# K60P144.net
KiCad netlist of a schematic drawn in Altium Designer
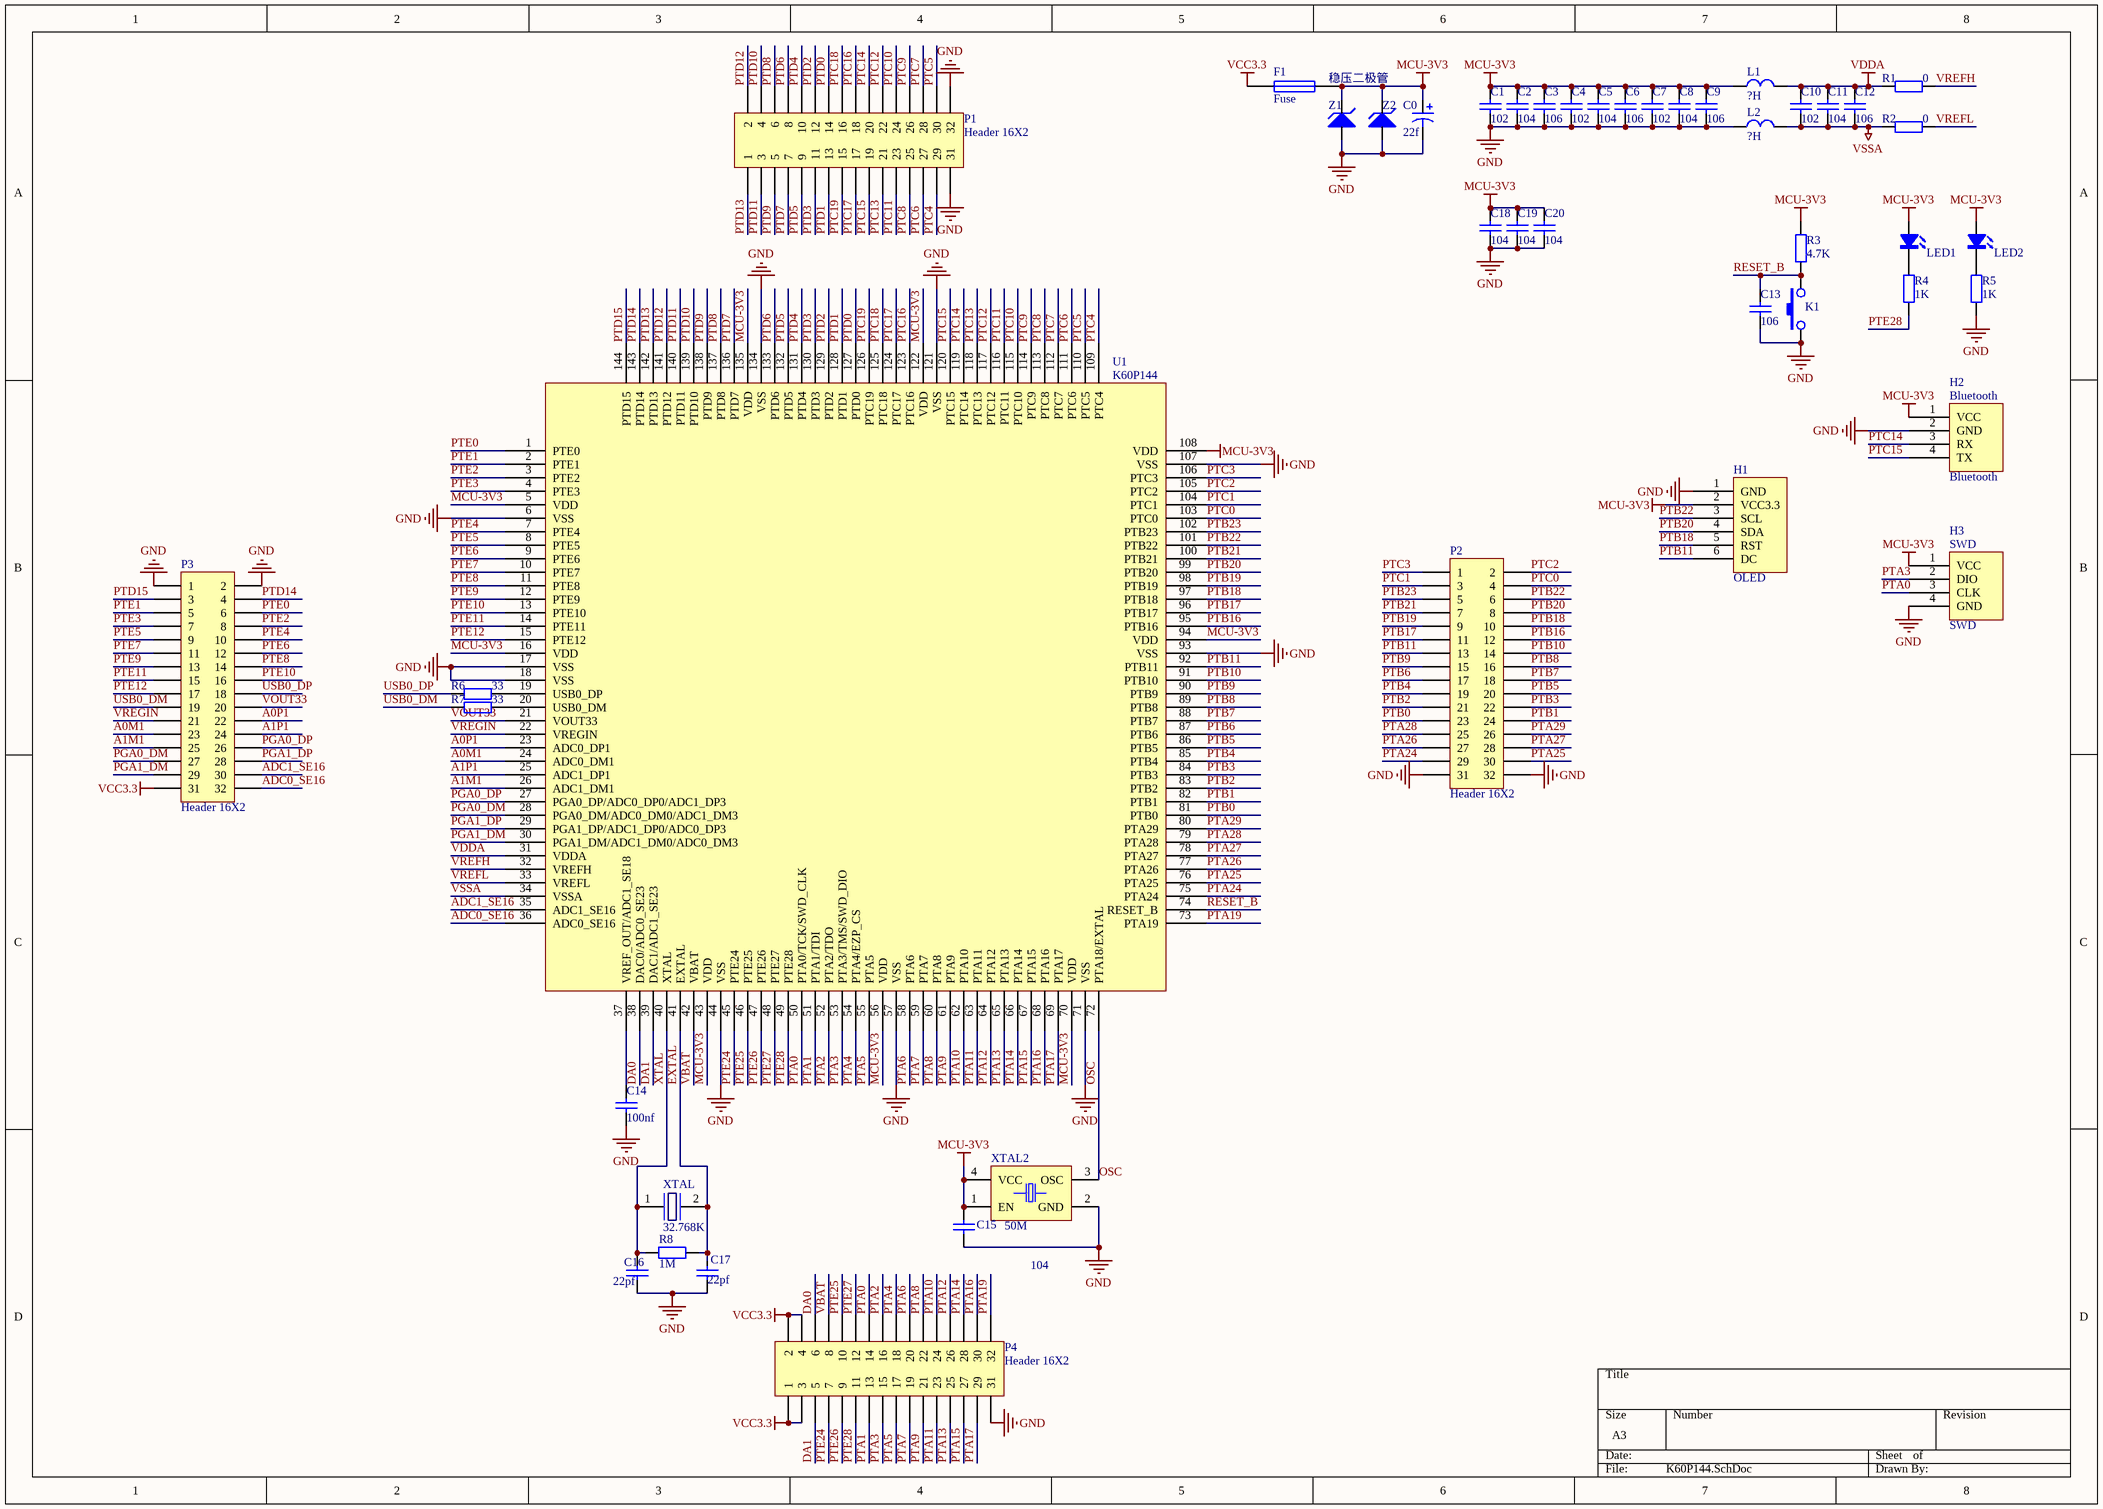
[diagram p0: K60P144.SchDoc]

(export (version "E")
  (design (tool "Eeschema 10.0.6"))
  (components
    (comp (ref "C0") (value "22f") (footprint "3528-B-TA") (libsource (lib "Bigbear") (part "CAP-TAN")))
    (comp (ref "C1") (value "102") (footprint "0805-0C") (libsource (lib "Bigbear") (part "CAP")))
    (comp (ref "C2") (value "104") (footprint "0805-0C") (libsource (lib "Bigbear") (part "CAP")))
    (comp (ref "C3") (value "106") (footprint "0805-0C") (libsource (lib "Bigbear") (part "CAP")))
    (comp (ref "C4") (value "102") (footprint "0805-0C") (libsource (lib "Bigbear") (part "CAP")))
    (comp (ref "C5") (value "104") (footprint "0805-0C") (libsource (lib "Bigbear") (part "CAP")))
    (comp (ref "C6") (value "106") (footprint "0805-0C") (libsource (lib "Bigbear") (part "CAP")))
    (comp (ref "C7") (value "102") (footprint "0805-0C") (libsource (lib "Bigbear") (part "CAP")))
    (comp (ref "C8") (value "104") (footprint "0805-0C") (libsource (lib "Bigbear") (part "CAP")))
    (comp (ref "C9") (value "106") (footprint "0805-0C") (libsource (lib "Bigbear") (part "CAP")))
    (comp (ref "C10") (value "102") (footprint "0805-0C") (libsource (lib "Bigbear") (part "CAP")))
    (comp (ref "C11") (value "104") (footprint "0805-0C") (libsource (lib "Bigbear") (part "CAP")))
    (comp (ref "C12") (value "106") (footprint "0805-0C") (libsource (lib "Bigbear") (part "CAP")))
    (comp (ref "C13") (value "106") (footprint "0805-0C") (libsource (lib "Bigbear") (part "CAP")))
    (comp (ref "C14") (value "100nf") (footprint "0805-0C") (libsource (lib "Bigbear") (part "CAP")))
    (comp (ref "C15") (value "104") (footprint "0805-0C") (libsource (lib "Bigbear") (part "CAP")))
    (comp (ref "C16") (value "22pf") (footprint "0805-0C") (libsource (lib "Bigbear") (part "CAP")))
    (comp (ref "C17") (value "22pf") (footprint "0805-0C") (libsource (lib "Bigbear") (part "CAP")))
    (comp (ref "C18") (value "104") (footprint "0805-0C") (libsource (lib "Bigbear") (part "CAP")))
    (comp (ref "C19") (value "104") (footprint "0805-0C") (libsource (lib "Bigbear") (part "CAP")))
    (comp (ref "C20") (value "104") (footprint "0805-0C") (libsource (lib "Bigbear") (part "CAP")))
    (comp (ref "F1") (value "Fuse") (footprint "1206R") (libsource (lib "Bigbear") (part "Fuse")))
    (comp (ref "H1") (value "OLED") (footprint "S0P6") (libsource (lib "Bigbear") (part "OLED")))
    (comp (ref "H2") (value "Bluetooth") (footprint "S0P4") (libsource (lib "Bigbear") (part "Bluetooth")))
    (comp (ref "H3") (value "SWD") (footprint "S0P4") (libsource (lib "Bigbear") (part "SWD")))
    (comp (ref "K1")
      (value "KEY")
      (footprint "SW_PB2_A1")
      (description "按键")
      (libsource (lib "Bigbear") (part "KEY"))
    )
    (comp (ref "L1")
      (value "?H")
      (footprint "1206C")
      (description "Inductor")
      (libsource (lib "Bigbear") (part "Inductor"))
    )
    (comp (ref "L2")
      (value "?H")
      (footprint "1206C")
      (description "Inductor")
      (libsource (lib "Bigbear") (part "Inductor"))
    )
    (comp (ref "LED1") (value "LED") (footprint "0805LED1") (libsource (lib "Bigbear") (part "LED")))
    (comp (ref "LED2") (value "LED") (footprint "0805LED1") (libsource (lib "Bigbear") (part "LED")))
    (comp (ref "P1") (value "Header 16X2") (footprint "201S2X16") (libsource (lib "") (part "Header 16X2_1")))
    (comp (ref "P2")
      (value "Header 16X2")
      (footprint "201S2X16")
      (libsource (lib "Bigbear") (part "Header 16X2"))
    )
    (comp (ref "P3")
      (value "Header 16X2")
      (footprint "201S2X16")
      (libsource (lib "Bigbear") (part "Header 16X2"))
    )
    (comp (ref "P4") (value "Header 16X2") (footprint "201S2X16") (libsource (lib "") (part "Header 16X2_1")))
    (comp (ref "R1") (value "0") (footprint "0603-r") (libsource (lib "Bigbear") (part "RES")))
    (comp (ref "R2") (value "0") (footprint "0603-r") (libsource (lib "Bigbear") (part "RES")))
    (comp (ref "R3") (value "4.7K") (footprint "0603-r") (libsource (lib "") (part "RES_1")))
    (comp (ref "R4") (value "1K") (footprint "0603-r") (libsource (lib "") (part "RES_1")))
    (comp (ref "R5") (value "1K") (footprint "0603-r") (libsource (lib "") (part "RES_1")))
    (comp (ref "R6") (value "33") (footprint "0603-r") (libsource (lib "Bigbear") (part "RES")))
    (comp (ref "R7") (value "33") (footprint "0603-r") (libsource (lib "Bigbear") (part "RES")))
    (comp (ref "R8") (value "1M") (footprint "0603-r") (libsource (lib "Bigbear") (part "RES")))
    (comp (ref "U1") (value "K60P144") (footprint "LQFP144") (libsource (lib "Bigbear") (part "K60P144")))
    (comp (ref "XTAL")
      (value "32.768K")
      (footprint "XTAL1-KHz-直插3")
      (libsource (lib "Bigbear") (part "XTAL-RTC"))
    )
    (comp (ref "XTAL2") (value "50M") (footprint "XTAL-3225") (libsource (lib "Bigbear") (part "XTAL")))
    (comp (ref "Z1") (value "Zener") (footprint "1206") (libsource (lib "Bigbear") (part "Zener")))
    (comp (ref "Z2") (value "稳压二极管") (footprint "1206") (libsource (lib "Bigbear") (part "Zener")))
  )
  (nets
    (net (code "1") (name "/A0M1") (class "Default")
      (node (ref "P3") (pin "23") (pinfunction "23_23") (pintype "passive"))
      (node (ref "U1") (pin "24") (pinfunction "ADC0_DM1_24") (pintype "passive"))
    )
    (net (code "2") (name "/A0P1") (class "Default")
      (node (ref "P3") (pin "22") (pinfunction "22_22") (pintype "passive"))
      (node (ref "U1") (pin "23") (pinfunction "ADC0_DP1_23") (pintype "passive"))
    )
    (net (code "3") (name "/A1M1") (class "Default")
      (node (ref "P3") (pin "25") (pinfunction "25_25") (pintype "passive"))
      (node (ref "U1") (pin "26") (pinfunction "ADC1_DM1_26") (pintype "passive"))
    )
    (net (code "4") (name "/A1P1") (class "Default")
      (node (ref "P3") (pin "24") (pinfunction "24_24") (pintype "passive"))
      (node (ref "U1") (pin "25") (pinfunction "ADC1_DP1_25") (pintype "passive"))
    )
    (net (code "5") (name "/ADC0_SE16") (class "Default")
      (node (ref "P3") (pin "32") (pinfunction "32_32") (pintype "passive"))
      (node (ref "U1") (pin "36") (pinfunction "ADC0_SE16_36") (pintype "passive"))
    )
    (net (code "6") (name "/ADC1_SE16") (class "Default")
      (node (ref "P3") (pin "30") (pinfunction "30_30") (pintype "passive"))
      (node (ref "U1") (pin "35") (pinfunction "ADC1_SE16_35") (pintype "passive"))
    )
    (net (code "7") (name "/DA0") (class "Default")
      (node (ref "P4") (pin "6") (pinfunction "6_6") (pintype "passive"))
      (node (ref "U1") (pin "38") (pinfunction "DAC0/ADC0_SE23_38") (pintype "passive"))
    )
    (net (code "8") (name "/DA1") (class "Default")
      (node (ref "P4") (pin "5") (pinfunction "5_5") (pintype "passive"))
      (node (ref "U1") (pin "39") (pinfunction "DAC1/ADC1_SE23_39") (pintype "passive"))
    )
    (net (code "9") (name "/EXTAL") (class "Default")
      (node (ref "C17") (pin "2") (pinfunction "2_2") (pintype "passive"))
      (node (ref "R8") (pin "2") (pinfunction "2_2") (pintype "passive"))
      (node (ref "U1") (pin "41") (pinfunction "EXTAL_41") (pintype "passive"))
      (node (ref "XTAL") (pin "2") (pintype "passive"))
    )
    (net (code "10") (name "/OSC") (class "Default")
      (node (ref "U1") (pin "72") (pinfunction "PTA18/EXTAL_72") (pintype "passive"))
      (node (ref "XTAL2") (pin "3") (pinfunction "OSC_3") (pintype "passive"))
    )
    (net (code "11") (name "/PGA0_DM") (class "Default")
      (node (ref "P3") (pin "27") (pinfunction "27_27") (pintype "passive"))
      (node (ref "U1") (pin "28") (pinfunction "PGA0_DM/ADC0_DM0/ADC1_DM3_28") (pintype "passive"))
    )
    (net (code "12") (name "/PGA0_DP") (class "Default")
      (node (ref "P3") (pin "26") (pinfunction "26_26") (pintype "passive"))
      (node (ref "U1") (pin "27") (pinfunction "PGA0_DP/ADC0_DP0/ADC1_DP3_27") (pintype "passive"))
    )
    (net (code "13") (name "/PGA1_DM") (class "Default")
      (node (ref "P3") (pin "29") (pinfunction "29_29") (pintype "passive"))
      (node (ref "U1") (pin "30") (pinfunction "PGA1_DM/ADC1_DM0/ADC0_DM3_30") (pintype "passive"))
    )
    (net (code "14") (name "/PGA1_DP") (class "Default")
      (node (ref "P3") (pin "28") (pinfunction "28_28") (pintype "passive"))
      (node (ref "U1") (pin "29") (pinfunction "PGA1_DP/ADC1_DP0/ADC0_DP3_29") (pintype "passive"))
    )
    (net (code "15") (name "/PTA0") (class "Default")
      (node (ref "H3") (pin "3") (pinfunction "CLK_3") (pintype "passive"))
      (node (ref "P4") (pin "14") (pinfunction "14_14") (pintype "passive"))
      (node (ref "U1") (pin "50") (pinfunction "PTA0/TCK/SWD_CLK_50") (pintype "passive"))
    )
    (net (code "16") (name "/PTA1") (class "Default")
      (node (ref "P4") (pin "13") (pinfunction "13_13") (pintype "passive"))
      (node (ref "U1") (pin "51") (pinfunction "PTA1/TDI_51") (pintype "passive"))
    )
    (net (code "17") (name "/PTA2") (class "Default")
      (node (ref "P4") (pin "16") (pinfunction "16_16") (pintype "passive"))
      (node (ref "U1") (pin "52") (pinfunction "PTA2/TDO_52") (pintype "passive"))
    )
    (net (code "18") (name "/PTA3") (class "Default")
      (node (ref "H3") (pin "2") (pinfunction "DIO_2") (pintype "passive"))
      (node (ref "P4") (pin "15") (pinfunction "15_15") (pintype "passive"))
      (node (ref "U1") (pin "53") (pinfunction "PTA3/TMS/SWD_DIO_53") (pintype "passive"))
    )
    (net (code "19") (name "/PTA4") (class "Default")
      (node (ref "P4") (pin "18") (pinfunction "18_18") (pintype "passive"))
      (node (ref "U1") (pin "54") (pinfunction "PTA4/EZP_CS_54") (pintype "passive"))
    )
    (net (code "20") (name "/PTA5") (class "Default")
      (node (ref "P4") (pin "17") (pinfunction "17_17") (pintype "passive"))
      (node (ref "U1") (pin "55") (pinfunction "PTA5_55") (pintype "passive"))
    )
    (net (code "21") (name "/PTA6") (class "Default")
      (node (ref "P4") (pin "20") (pinfunction "20_20") (pintype "passive"))
      (node (ref "U1") (pin "58") (pinfunction "PTA6_58") (pintype "passive"))
    )
    (net (code "22") (name "/PTA7") (class "Default")
      (node (ref "P4") (pin "19") (pinfunction "19_19") (pintype "passive"))
      (node (ref "U1") (pin "59") (pinfunction "PTA7_59") (pintype "passive"))
    )
    (net (code "23") (name "/PTA8") (class "Default")
      (node (ref "P4") (pin "22") (pinfunction "22_22") (pintype "passive"))
      (node (ref "U1") (pin "60") (pinfunction "PTA8_60") (pintype "passive"))
    )
    (net (code "24") (name "/PTA9") (class "Default")
      (node (ref "P4") (pin "21") (pinfunction "21_21") (pintype "passive"))
      (node (ref "U1") (pin "61") (pinfunction "PTA9_61") (pintype "passive"))
    )
    (net (code "25") (name "/PTA10") (class "Default")
      (node (ref "P4") (pin "24") (pinfunction "24_24") (pintype "passive"))
      (node (ref "U1") (pin "62") (pinfunction "PTA10_62") (pintype "passive"))
    )
    (net (code "26") (name "/PTA11") (class "Default")
      (node (ref "P4") (pin "23") (pinfunction "23_23") (pintype "passive"))
      (node (ref "U1") (pin "63") (pinfunction "PTA11_63") (pintype "passive"))
    )
    (net (code "27") (name "/PTA12") (class "Default")
      (node (ref "P4") (pin "26") (pinfunction "26_26") (pintype "passive"))
      (node (ref "U1") (pin "64") (pinfunction "PTA12_64") (pintype "passive"))
    )
    (net (code "28") (name "/PTA13") (class "Default")
      (node (ref "P4") (pin "25") (pinfunction "25_25") (pintype "passive"))
      (node (ref "U1") (pin "65") (pinfunction "PTA13_65") (pintype "passive"))
    )
    (net (code "29") (name "/PTA14") (class "Default")
      (node (ref "P4") (pin "28") (pinfunction "28_28") (pintype "passive"))
      (node (ref "U1") (pin "66") (pinfunction "PTA14_66") (pintype "passive"))
    )
    (net (code "30") (name "/PTA15") (class "Default")
      (node (ref "P4") (pin "27") (pinfunction "27_27") (pintype "passive"))
      (node (ref "U1") (pin "67") (pinfunction "PTA15_67") (pintype "passive"))
    )
    (net (code "31") (name "/PTA16") (class "Default")
      (node (ref "P4") (pin "30") (pinfunction "30_30") (pintype "passive"))
      (node (ref "U1") (pin "68") (pinfunction "PTA16_68") (pintype "passive"))
    )
    (net (code "32") (name "/PTA17") (class "Default")
      (node (ref "P4") (pin "29") (pinfunction "29_29") (pintype "passive"))
      (node (ref "U1") (pin "69") (pinfunction "PTA17_69") (pintype "passive"))
    )
    (net (code "33") (name "/PTA19") (class "Default")
      (node (ref "P4") (pin "32") (pinfunction "32_32") (pintype "passive"))
      (node (ref "U1") (pin "73") (pinfunction "PTA19_73") (pintype "passive"))
    )
    (net (code "34") (name "/PTA24") (class "Default")
      (node (ref "P2") (pin "29") (pinfunction "29_29") (pintype "passive"))
      (node (ref "U1") (pin "75") (pinfunction "PTA24_75") (pintype "passive"))
    )
    (net (code "35") (name "/PTA25") (class "Default")
      (node (ref "P2") (pin "30") (pinfunction "30_30") (pintype "passive"))
      (node (ref "U1") (pin "76") (pinfunction "PTA25_76") (pintype "passive"))
    )
    (net (code "36") (name "/PTA26") (class "Default")
      (node (ref "P2") (pin "27") (pinfunction "27_27") (pintype "passive"))
      (node (ref "U1") (pin "77") (pinfunction "PTA26_77") (pintype "passive"))
    )
    (net (code "37") (name "/PTA27") (class "Default")
      (node (ref "P2") (pin "28") (pinfunction "28_28") (pintype "passive"))
      (node (ref "U1") (pin "78") (pinfunction "PTA27_78") (pintype "passive"))
    )
    (net (code "38") (name "/PTA28") (class "Default")
      (node (ref "P2") (pin "25") (pinfunction "25_25") (pintype "passive"))
      (node (ref "U1") (pin "79") (pinfunction "PTA28_79") (pintype "passive"))
    )
    (net (code "39") (name "/PTA29") (class "Default")
      (node (ref "P2") (pin "26") (pinfunction "26_26") (pintype "passive"))
      (node (ref "U1") (pin "80") (pinfunction "PTA29_80") (pintype "passive"))
    )
    (net (code "40") (name "/PTB0") (class "Default")
      (node (ref "P2") (pin "23") (pinfunction "23_23") (pintype "passive"))
      (node (ref "U1") (pin "81") (pinfunction "PTB0_81") (pintype "passive"))
    )
    (net (code "41") (name "/PTB1") (class "Default")
      (node (ref "P2") (pin "24") (pinfunction "24_24") (pintype "passive"))
      (node (ref "U1") (pin "82") (pinfunction "PTB1_82") (pintype "passive"))
    )
    (net (code "42") (name "/PTB2") (class "Default")
      (node (ref "P2") (pin "21") (pinfunction "21_21") (pintype "passive"))
      (node (ref "U1") (pin "83") (pinfunction "PTB2_83") (pintype "passive"))
    )
    (net (code "43") (name "/PTB3") (class "Default")
      (node (ref "P2") (pin "22") (pinfunction "22_22") (pintype "passive"))
      (node (ref "U1") (pin "84") (pinfunction "PTB3_84") (pintype "passive"))
    )
    (net (code "44") (name "/PTB4") (class "Default")
      (node (ref "P2") (pin "19") (pinfunction "19_19") (pintype "passive"))
      (node (ref "U1") (pin "85") (pinfunction "PTB4_85") (pintype "passive"))
    )
    (net (code "45") (name "/PTB5") (class "Default")
      (node (ref "P2") (pin "20") (pinfunction "20_20") (pintype "passive"))
      (node (ref "U1") (pin "86") (pinfunction "PTB5_86") (pintype "passive"))
    )
    (net (code "46") (name "/PTB6") (class "Default")
      (node (ref "P2") (pin "17") (pinfunction "17_17") (pintype "passive"))
      (node (ref "U1") (pin "87") (pinfunction "PTB6_87") (pintype "passive"))
    )
    (net (code "47") (name "/PTB7") (class "Default")
      (node (ref "P2") (pin "18") (pinfunction "18_18") (pintype "passive"))
      (node (ref "U1") (pin "88") (pinfunction "PTB7_88") (pintype "passive"))
    )
    (net (code "48") (name "/PTB8") (class "Default")
      (node (ref "P2") (pin "16") (pinfunction "16_16") (pintype "passive"))
      (node (ref "U1") (pin "89") (pinfunction "PTB8_89") (pintype "passive"))
    )
    (net (code "49") (name "/PTB9") (class "Default")
      (node (ref "P2") (pin "15") (pinfunction "15_15") (pintype "passive"))
      (node (ref "U1") (pin "90") (pinfunction "PTB9_90") (pintype "passive"))
    )
    (net (code "50") (name "/PTB10") (class "Default")
      (node (ref "P2") (pin "14") (pinfunction "14_14") (pintype "passive"))
      (node (ref "U1") (pin "91") (pinfunction "PTB10_91") (pintype "passive"))
    )
    (net (code "51") (name "/PTB11") (class "Default")
      (node (ref "H1") (pin "6") (pinfunction "DC_6") (pintype "passive"))
      (node (ref "P2") (pin "13") (pinfunction "13_13") (pintype "passive"))
      (node (ref "U1") (pin "92") (pinfunction "PTB11_92") (pintype "passive"))
    )
    (net (code "52") (name "/PTB16") (class "Default")
      (node (ref "P2") (pin "12") (pinfunction "12_12") (pintype "passive"))
      (node (ref "U1") (pin "95") (pinfunction "PTB16_95") (pintype "passive"))
    )
    (net (code "53") (name "/PTB17") (class "Default")
      (node (ref "P2") (pin "11") (pinfunction "11_11") (pintype "passive"))
      (node (ref "U1") (pin "96") (pinfunction "PTB17_96") (pintype "passive"))
    )
    (net (code "54") (name "/PTB18") (class "Default")
      (node (ref "H1") (pin "5") (pinfunction "RST_5") (pintype "passive"))
      (node (ref "P2") (pin "10") (pinfunction "10_10") (pintype "passive"))
      (node (ref "U1") (pin "97") (pinfunction "PTB18_97") (pintype "passive"))
    )
    (net (code "55") (name "/PTB19") (class "Default")
      (node (ref "P2") (pin "9") (pinfunction "9_9") (pintype "passive"))
      (node (ref "U1") (pin "98") (pinfunction "PTB19_98") (pintype "passive"))
    )
    (net (code "56") (name "/PTB20") (class "Default")
      (node (ref "H1") (pin "4") (pinfunction "SDA_4") (pintype "passive"))
      (node (ref "P2") (pin "8") (pinfunction "8_8") (pintype "passive"))
      (node (ref "U1") (pin "99") (pinfunction "PTB20_99") (pintype "passive"))
    )
    (net (code "57") (name "/PTB21") (class "Default")
      (node (ref "P2") (pin "7") (pinfunction "7_7") (pintype "passive"))
      (node (ref "U1") (pin "100") (pinfunction "PTB21_100") (pintype "passive"))
    )
    (net (code "58") (name "/PTB22") (class "Default")
      (node (ref "H1") (pin "3") (pinfunction "SCL_3") (pintype "passive"))
      (node (ref "P2") (pin "6") (pinfunction "6_6") (pintype "passive"))
      (node (ref "U1") (pin "101") (pinfunction "PTB22_101") (pintype "passive"))
    )
    (net (code "59") (name "/PTB23") (class "Default")
      (node (ref "P2") (pin "5") (pinfunction "5_5") (pintype "passive"))
      (node (ref "U1") (pin "102") (pinfunction "PTB23_102") (pintype "passive"))
    )
    (net (code "60") (name "/PTC0") (class "Default")
      (node (ref "P2") (pin "4") (pinfunction "4_4") (pintype "passive"))
      (node (ref "U1") (pin "103") (pinfunction "PTC0_103") (pintype "passive"))
    )
    (net (code "61") (name "/PTC1") (class "Default")
      (node (ref "P2") (pin "3") (pinfunction "3_3") (pintype "passive"))
      (node (ref "U1") (pin "104") (pinfunction "PTC1_104") (pintype "passive"))
    )
    (net (code "62") (name "/PTC2") (class "Default")
      (node (ref "P2") (pin "2") (pinfunction "2_2") (pintype "passive"))
      (node (ref "U1") (pin "105") (pinfunction "PTC2_105") (pintype "passive"))
    )
    (net (code "63") (name "/PTC3") (class "Default")
      (node (ref "P2") (pin "1") (pinfunction "1_1") (pintype "passive"))
      (node (ref "U1") (pin "106") (pinfunction "PTC3_106") (pintype "passive"))
    )
    (net (code "64") (name "/PTC4") (class "Default")
      (node (ref "P1") (pin "29") (pinfunction "29_29") (pintype "passive"))
      (node (ref "U1") (pin "109") (pinfunction "PTC4_109") (pintype "passive"))
    )
    (net (code "65") (name "/PTC5") (class "Default")
      (node (ref "P1") (pin "30") (pinfunction "30_30") (pintype "passive"))
      (node (ref "U1") (pin "110") (pinfunction "PTC5_110") (pintype "passive"))
    )
    (net (code "66") (name "/PTC6") (class "Default")
      (node (ref "P1") (pin "27") (pinfunction "27_27") (pintype "passive"))
      (node (ref "U1") (pin "111") (pinfunction "PTC6_111") (pintype "passive"))
    )
    (net (code "67") (name "/PTC7") (class "Default")
      (node (ref "P1") (pin "28") (pinfunction "28_28") (pintype "passive"))
      (node (ref "U1") (pin "112") (pinfunction "PTC7_112") (pintype "passive"))
    )
    (net (code "68") (name "/PTC8") (class "Default")
      (node (ref "P1") (pin "25") (pinfunction "25_25") (pintype "passive"))
      (node (ref "U1") (pin "113") (pinfunction "PTC8_113") (pintype "passive"))
    )
    (net (code "69") (name "/PTC9") (class "Default")
      (node (ref "P1") (pin "26") (pinfunction "26_26") (pintype "passive"))
      (node (ref "U1") (pin "114") (pinfunction "PTC9_114") (pintype "passive"))
    )
    (net (code "70") (name "/PTC10") (class "Default")
      (node (ref "P1") (pin "24") (pinfunction "24_24") (pintype "passive"))
      (node (ref "U1") (pin "115") (pinfunction "PTC10_115") (pintype "passive"))
    )
    (net (code "71") (name "/PTC11") (class "Default")
      (node (ref "P1") (pin "23") (pinfunction "23_23") (pintype "passive"))
      (node (ref "U1") (pin "116") (pinfunction "PTC11_116") (pintype "passive"))
    )
    (net (code "72") (name "/PTC12") (class "Default")
      (node (ref "P1") (pin "22") (pinfunction "22_22") (pintype "passive"))
      (node (ref "U1") (pin "117") (pinfunction "PTC12_117") (pintype "passive"))
    )
    (net (code "73") (name "/PTC13") (class "Default")
      (node (ref "P1") (pin "21") (pinfunction "21_21") (pintype "passive"))
      (node (ref "U1") (pin "118") (pinfunction "PTC13_118") (pintype "passive"))
    )
    (net (code "74") (name "/PTC14") (class "Default")
      (node (ref "H2") (pin "3") (pinfunction "RX_3") (pintype "passive"))
      (node (ref "P1") (pin "20") (pinfunction "20_20") (pintype "passive"))
      (node (ref "U1") (pin "119") (pinfunction "PTC14_119") (pintype "passive"))
    )
    (net (code "75") (name "/PTC15") (class "Default")
      (node (ref "H2") (pin "4") (pinfunction "TX_4") (pintype "passive"))
      (node (ref "P1") (pin "19") (pinfunction "19_19") (pintype "passive"))
      (node (ref "U1") (pin "120") (pinfunction "PTC15_120") (pintype "passive"))
    )
    (net (code "76") (name "/PTC16") (class "Default")
      (node (ref "P1") (pin "18") (pinfunction "18_18") (pintype "passive"))
      (node (ref "U1") (pin "123") (pinfunction "PTC16_123") (pintype "passive"))
    )
    (net (code "77") (name "/PTC17") (class "Default")
      (node (ref "P1") (pin "17") (pinfunction "17_17") (pintype "passive"))
      (node (ref "U1") (pin "124") (pinfunction "PTC17_124") (pintype "passive"))
    )
    (net (code "78") (name "/PTC18") (class "Default")
      (node (ref "P1") (pin "16") (pinfunction "16_16") (pintype "passive"))
      (node (ref "U1") (pin "125") (pinfunction "PTC18_125") (pintype "passive"))
    )
    (net (code "79") (name "/PTC19") (class "Default")
      (node (ref "P1") (pin "15") (pinfunction "15_15") (pintype "passive"))
      (node (ref "U1") (pin "126") (pinfunction "PTC19_126") (pintype "passive"))
    )
    (net (code "80") (name "/PTD0") (class "Default")
      (node (ref "P1") (pin "14") (pinfunction "14_14") (pintype "passive"))
      (node (ref "U1") (pin "127") (pinfunction "PTD0_127") (pintype "passive"))
    )
    (net (code "81") (name "/PTD1") (class "Default")
      (node (ref "P1") (pin "13") (pinfunction "13_13") (pintype "passive"))
      (node (ref "U1") (pin "128") (pinfunction "PTD1_128") (pintype "passive"))
    )
    (net (code "82") (name "/PTD2") (class "Default")
      (node (ref "P1") (pin "12") (pinfunction "12_12") (pintype "passive"))
      (node (ref "U1") (pin "129") (pinfunction "PTD2_129") (pintype "passive"))
    )
    (net (code "83") (name "/PTD3") (class "Default")
      (node (ref "P1") (pin "11") (pinfunction "11_11") (pintype "passive"))
      (node (ref "U1") (pin "130") (pinfunction "PTD3_130") (pintype "passive"))
    )
    (net (code "84") (name "/PTD4") (class "Default")
      (node (ref "P1") (pin "10") (pinfunction "10_10") (pintype "passive"))
      (node (ref "U1") (pin "131") (pinfunction "PTD4_131") (pintype "passive"))
    )
    (net (code "85") (name "/PTD5") (class "Default")
      (node (ref "P1") (pin "9") (pinfunction "9_9") (pintype "passive"))
      (node (ref "U1") (pin "132") (pinfunction "PTD5_132") (pintype "passive"))
    )
    (net (code "86") (name "/PTD6") (class "Default")
      (node (ref "P1") (pin "8") (pinfunction "8_8") (pintype "passive"))
      (node (ref "U1") (pin "133") (pinfunction "PTD6_133") (pintype "passive"))
    )
    (net (code "87") (name "/PTD7") (class "Default")
      (node (ref "P1") (pin "7") (pinfunction "7_7") (pintype "passive"))
      (node (ref "U1") (pin "136") (pinfunction "PTD7_136") (pintype "passive"))
    )
    (net (code "88") (name "/PTD8") (class "Default")
      (node (ref "P1") (pin "6") (pinfunction "6_6") (pintype "passive"))
      (node (ref "U1") (pin "137") (pinfunction "PTD8_137") (pintype "passive"))
    )
    (net (code "89") (name "/PTD9") (class "Default")
      (node (ref "P1") (pin "5") (pinfunction "5_5") (pintype "passive"))
      (node (ref "U1") (pin "138") (pinfunction "PTD9_138") (pintype "passive"))
    )
    (net (code "90") (name "/PTD10") (class "Default")
      (node (ref "P1") (pin "4") (pinfunction "4_4") (pintype "passive"))
      (node (ref "U1") (pin "139") (pinfunction "PTD10_139") (pintype "passive"))
    )
    (net (code "91") (name "/PTD11") (class "Default")
      (node (ref "P1") (pin "3") (pinfunction "3_3") (pintype "passive"))
      (node (ref "U1") (pin "140") (pinfunction "PTD11_140") (pintype "passive"))
    )
    (net (code "92") (name "/PTD12") (class "Default")
      (node (ref "P1") (pin "2") (pinfunction "2_2") (pintype "passive"))
      (node (ref "U1") (pin "141") (pinfunction "PTD12_141") (pintype "passive"))
    )
    (net (code "93") (name "/PTD13") (class "Default")
      (node (ref "P1") (pin "1") (pinfunction "1_1") (pintype "passive"))
      (node (ref "U1") (pin "142") (pinfunction "PTD13_142") (pintype "passive"))
    )
    (net (code "94") (name "/PTD14") (class "Default")
      (node (ref "P3") (pin "4") (pinfunction "4_4") (pintype "passive"))
      (node (ref "U1") (pin "143") (pinfunction "PTD14_143") (pintype "passive"))
    )
    (net (code "95") (name "/PTD15") (class "Default")
      (node (ref "P3") (pin "3") (pinfunction "3_3") (pintype "passive"))
      (node (ref "U1") (pin "144") (pinfunction "PTD15_144") (pintype "passive"))
    )
    (net (code "96") (name "/PTE0") (class "Default")
      (node (ref "P3") (pin "6") (pinfunction "6_6") (pintype "passive"))
      (node (ref "U1") (pin "1") (pinfunction "PTE0_1") (pintype "passive"))
    )
    (net (code "97") (name "/PTE1") (class "Default")
      (node (ref "P3") (pin "5") (pinfunction "5_5") (pintype "passive"))
      (node (ref "U1") (pin "2") (pinfunction "PTE1_2") (pintype "passive"))
    )
    (net (code "98") (name "/PTE2") (class "Default")
      (node (ref "P3") (pin "8") (pinfunction "8_8") (pintype "passive"))
      (node (ref "U1") (pin "3") (pinfunction "PTE2_3") (pintype "passive"))
    )
    (net (code "99") (name "/PTE3") (class "Default")
      (node (ref "P3") (pin "7") (pinfunction "7_7") (pintype "passive"))
      (node (ref "U1") (pin "4") (pinfunction "PTE3_4") (pintype "passive"))
    )
    (net (code "100") (name "/PTE4") (class "Default")
      (node (ref "P3") (pin "10") (pinfunction "10_10") (pintype "passive"))
      (node (ref "U1") (pin "7") (pinfunction "PTE4_7") (pintype "passive"))
    )
    (net (code "101") (name "/PTE5") (class "Default")
      (node (ref "P3") (pin "9") (pinfunction "9_9") (pintype "passive"))
      (node (ref "U1") (pin "8") (pinfunction "PTE5_8") (pintype "passive"))
    )
    (net (code "102") (name "/PTE6") (class "Default")
      (node (ref "P3") (pin "12") (pinfunction "12_12") (pintype "passive"))
      (node (ref "U1") (pin "9") (pinfunction "PTE6_9") (pintype "passive"))
    )
    (net (code "103") (name "/PTE7") (class "Default")
      (node (ref "P3") (pin "11") (pinfunction "11_11") (pintype "passive"))
      (node (ref "U1") (pin "10") (pinfunction "PTE7_10") (pintype "passive"))
    )
    (net (code "104") (name "/PTE8") (class "Default")
      (node (ref "P3") (pin "14") (pinfunction "14_14") (pintype "passive"))
      (node (ref "U1") (pin "11") (pinfunction "PTE8_11") (pintype "passive"))
    )
    (net (code "105") (name "/PTE9") (class "Default")
      (node (ref "P3") (pin "13") (pinfunction "13_13") (pintype "passive"))
      (node (ref "U1") (pin "12") (pinfunction "PTE9_12") (pintype "passive"))
    )
    (net (code "106") (name "/PTE10") (class "Default")
      (node (ref "P3") (pin "16") (pinfunction "16_16") (pintype "passive"))
      (node (ref "U1") (pin "13") (pinfunction "PTE10_13") (pintype "passive"))
    )
    (net (code "107") (name "/PTE11") (class "Default")
      (node (ref "P3") (pin "15") (pinfunction "15_15") (pintype "passive"))
      (node (ref "U1") (pin "14") (pinfunction "PTE11_14") (pintype "passive"))
    )
    (net (code "108") (name "/PTE12") (class "Default")
      (node (ref "P3") (pin "17") (pinfunction "17_17") (pintype "passive"))
      (node (ref "U1") (pin "15") (pinfunction "PTE12_15") (pintype "passive"))
    )
    (net (code "109") (name "/PTE24") (class "Default")
      (node (ref "P4") (pin "7") (pinfunction "7_7") (pintype "passive"))
      (node (ref "U1") (pin "45") (pinfunction "PTE24_45") (pintype "passive"))
    )
    (net (code "110") (name "/PTE25") (class "Default")
      (node (ref "P4") (pin "10") (pinfunction "10_10") (pintype "passive"))
      (node (ref "U1") (pin "46") (pinfunction "PTE25_46") (pintype "passive"))
    )
    (net (code "111") (name "/PTE26") (class "Default")
      (node (ref "P4") (pin "9") (pinfunction "9_9") (pintype "passive"))
      (node (ref "U1") (pin "47") (pinfunction "PTE26_47") (pintype "passive"))
    )
    (net (code "112") (name "/PTE27") (class "Default")
      (node (ref "P4") (pin "12") (pinfunction "12_12") (pintype "passive"))
      (node (ref "U1") (pin "48") (pinfunction "PTE27_48") (pintype "passive"))
    )
    (net (code "113") (name "/PTE28") (class "Default")
      (node (ref "P4") (pin "11") (pinfunction "11_11") (pintype "passive"))
      (node (ref "R4") (pin "1") (pinfunction "1_1") (pintype "passive"))
      (node (ref "U1") (pin "49") (pinfunction "PTE28_49") (pintype "passive"))
    )
    (net (code "114") (name "/RESET_B") (class "Default")
      (node (ref "C13") (pin "2") (pinfunction "2_2") (pintype "passive"))
      (node (ref "K1") (pin "2") (pinfunction "2_2") (pintype "passive"))
      (node (ref "R3") (pin "1") (pinfunction "1_1") (pintype "passive"))
      (node (ref "U1") (pin "74") (pinfunction "RESET_B_74") (pintype "passive"))
    )
    (net (code "115") (name "/USB0_DM") (class "Default")
      (node (ref "P3") (pin "19") (pinfunction "19_19") (pintype "passive"))
      (node (ref "R7") (pin "1") (pinfunction "1_1") (pintype "passive"))
    )
    (net (code "116") (name "/USB0_DP") (class "Default")
      (node (ref "P3") (pin "18") (pinfunction "18_18") (pintype "passive"))
      (node (ref "R6") (pin "1") (pinfunction "1_1") (pintype "passive"))
    )
    (net (code "117") (name "/VBAT") (class "Default")
      (node (ref "P4") (pin "8") (pinfunction "8_8") (pintype "passive"))
      (node (ref "U1") (pin "42") (pinfunction "VBAT_42") (pintype "passive"))
    )
    (net (code "118") (name "/VOUT33") (class "Default")
      (node (ref "P3") (pin "20") (pinfunction "20_20") (pintype "passive"))
      (node (ref "U1") (pin "21") (pinfunction "VOUT33_21") (pintype "passive"))
    )
    (net (code "119") (name "/VREFH") (class "Default")
      (node (ref "R1") (pin "2") (pinfunction "2_2") (pintype "passive"))
      (node (ref "U1") (pin "32") (pinfunction "VREFH_32") (pintype "passive"))
    )
    (net (code "120") (name "/VREFL") (class "Default")
      (node (ref "R2") (pin "2") (pinfunction "2_2") (pintype "passive"))
      (node (ref "U1") (pin "33") (pinfunction "VREFL_33") (pintype "passive"))
    )
    (net (code "121") (name "/VREGIN") (class "Default")
      (node (ref "P3") (pin "21") (pinfunction "21_21") (pintype "passive"))
      (node (ref "U1") (pin "22") (pinfunction "VREGIN_22") (pintype "passive"))
    )
    (net (code "122") (name "/XTAL") (class "Default")
      (node (ref "C16") (pin "2") (pinfunction "2_2") (pintype "passive"))
      (node (ref "R8") (pin "1") (pinfunction "1_1") (pintype "passive"))
      (node (ref "U1") (pin "40") (pinfunction "XTAL_40") (pintype "passive"))
      (node (ref "XTAL") (pin "1") (pintype "power_in"))
    )
    (net (code "123") (name "GND") (class "Default")
      (node (ref "C0") (pin "2") (pinfunction "2_2") (pintype "passive"))
      (node (ref "C1") (pin "1") (pinfunction "1_1") (pintype "passive"))
      (node (ref "C13") (pin "1") (pinfunction "1_1") (pintype "passive"))
      (node (ref "C14") (pin "1") (pinfunction "1_1") (pintype "passive"))
      (node (ref "C15") (pin "1") (pinfunction "1_1") (pintype "passive"))
      (node (ref "C16") (pin "1") (pinfunction "1_1") (pintype "passive"))
      (node (ref "C17") (pin "1") (pinfunction "1_1") (pintype "passive"))
      (node (ref "C18") (pin "1") (pinfunction "1_1") (pintype "passive"))
      (node (ref "C19") (pin "1") (pinfunction "1_1") (pintype "passive"))
      (node (ref "C2") (pin "1") (pinfunction "1_1") (pintype "passive"))
      (node (ref "C20") (pin "1") (pinfunction "1_1") (pintype "passive"))
      (node (ref "C3") (pin "1") (pinfunction "1_1") (pintype "passive"))
      (node (ref "C4") (pin "1") (pinfunction "1_1") (pintype "passive"))
      (node (ref "C5") (pin "1") (pinfunction "1_1") (pintype "passive"))
      (node (ref "C6") (pin "1") (pinfunction "1_1") (pintype "passive"))
      (node (ref "C7") (pin "1") (pinfunction "1_1") (pintype "passive"))
      (node (ref "C8") (pin "1") (pinfunction "1_1") (pintype "passive"))
      (node (ref "C9") (pin "1") (pinfunction "1_1") (pintype "passive"))
      (node (ref "H1") (pin "1") (pinfunction "GND_1") (pintype "passive"))
      (node (ref "H2") (pin "2") (pinfunction "GND_2") (pintype "passive"))
      (node (ref "H3") (pin "4") (pinfunction "GND_4") (pintype "passive"))
      (node (ref "K1") (pin "1") (pinfunction "1_1") (pintype "passive"))
      (node (ref "L2") (pin "1") (pinfunction "1_1") (pintype "passive"))
      (node (ref "P1") (pin "31") (pinfunction "31_31") (pintype "passive"))
      (node (ref "P1") (pin "32") (pinfunction "32_32") (pintype "passive"))
      (node (ref "P2") (pin "31") (pinfunction "31_31") (pintype "passive"))
      (node (ref "P2") (pin "32") (pinfunction "32_32") (pintype "passive"))
      (node (ref "P3") (pin "1") (pinfunction "1_1") (pintype "passive"))
      (node (ref "P3") (pin "2") (pinfunction "2_2") (pintype "passive"))
      (node (ref "P4") (pin "31") (pinfunction "31_31") (pintype "passive"))
      (node (ref "R5") (pin "1") (pinfunction "1_1") (pintype "passive"))
      (node (ref "U1") (pin "107") (pinfunction "VSS_107") (pintype "passive"))
      (node (ref "U1") (pin "121") (pinfunction "VSS_121") (pintype "passive"))
      (node (ref "U1") (pin "134") (pinfunction "VSS_134") (pintype "passive"))
      (node (ref "U1") (pin "17") (pinfunction "VSS_17") (pintype "passive"))
      (node (ref "U1") (pin "18") (pinfunction "VSS_18") (pintype "passive"))
      (node (ref "U1") (pin "44") (pinfunction "VSS_44") (pintype "passive"))
      (node (ref "U1") (pin "57") (pinfunction "VSS_57") (pintype "passive"))
      (node (ref "U1") (pin "6") (pinfunction "VSS_6") (pintype "passive"))
      (node (ref "U1") (pin "71") (pinfunction "VSS_71") (pintype "passive"))
      (node (ref "U1") (pin "93") (pinfunction "VSS_93") (pintype "passive"))
      (node (ref "XTAL2") (pin "2") (pinfunction "GND_2") (pintype "passive"))
      (node (ref "Z1") (pin "1") (pinfunction "A_1") (pintype "passive"))
      (node (ref "Z2") (pin "1") (pinfunction "A_1") (pintype "passive"))
    )
    (net (code "124") (name "MCU-3V3") (class "Default")
      (node (ref "C0") (pin "1") (pinfunction "1_1") (pintype "passive"))
      (node (ref "C1") (pin "2") (pinfunction "2_2") (pintype "passive"))
      (node (ref "C15") (pin "2") (pinfunction "2_2") (pintype "passive"))
      (node (ref "C18") (pin "2") (pinfunction "2_2") (pintype "passive"))
      (node (ref "C19") (pin "2") (pinfunction "2_2") (pintype "passive"))
      (node (ref "C2") (pin "2") (pinfunction "2_2") (pintype "passive"))
      (node (ref "C20") (pin "2") (pinfunction "2_2") (pintype "passive"))
      (node (ref "C3") (pin "2") (pinfunction "2_2") (pintype "passive"))
      (node (ref "C4") (pin "2") (pinfunction "2_2") (pintype "passive"))
      (node (ref "C5") (pin "2") (pinfunction "2_2") (pintype "passive"))
      (node (ref "C6") (pin "2") (pinfunction "2_2") (pintype "passive"))
      (node (ref "C7") (pin "2") (pinfunction "2_2") (pintype "passive"))
      (node (ref "C8") (pin "2") (pinfunction "2_2") (pintype "passive"))
      (node (ref "C9") (pin "2") (pinfunction "2_2") (pintype "passive"))
      (node (ref "F1") (pin "1") (pinfunction "1_1") (pintype "passive"))
      (node (ref "H1") (pin "2") (pinfunction "VCC3.3_2") (pintype "passive"))
      (node (ref "H2") (pin "1") (pinfunction "VCC_1") (pintype "passive"))
      (node (ref "H3") (pin "1") (pinfunction "VCC_1") (pintype "passive"))
      (node (ref "L1") (pin "1") (pinfunction "1_1") (pintype "passive"))
      (node (ref "LED1") (pin "1") (pinfunction "K_1") (pintype "passive"))
      (node (ref "LED2") (pin "1") (pinfunction "K_1") (pintype "passive"))
      (node (ref "R3") (pin "2") (pinfunction "2_2") (pintype "passive"))
      (node (ref "U1") (pin "108") (pinfunction "VDD_108") (pintype "passive"))
      (node (ref "U1") (pin "122") (pinfunction "VDD_122") (pintype "passive"))
      (node (ref "U1") (pin "135") (pinfunction "VDD_135") (pintype "passive"))
      (node (ref "U1") (pin "16") (pinfunction "VDD_16") (pintype "passive"))
      (node (ref "U1") (pin "43") (pinfunction "VDD_43") (pintype "passive"))
      (node (ref "U1") (pin "5") (pinfunction "VDD_5") (pintype "passive"))
      (node (ref "U1") (pin "56") (pinfunction "VDD_56") (pintype "passive"))
      (node (ref "U1") (pin "70") (pinfunction "VDD_70") (pintype "passive"))
      (node (ref "U1") (pin "94") (pinfunction "VDD_94") (pintype "passive"))
      (node (ref "XTAL2") (pin "1") (pinfunction "EN_1") (pintype "passive"))
      (node (ref "XTAL2") (pin "4") (pinfunction "VCC_4") (pintype "power_in"))
      (node (ref "Z1") (pin "2") (pinfunction "K_2") (pintype "passive"))
      (node (ref "Z2") (pin "2") (pinfunction "K_2") (pintype "passive"))
    )
    (net (code "125") (name "Net-(LED1-A)") (class "Default")
      (node (ref "LED1") (pin "2") (pinfunction "A_2") (pintype "passive"))
      (node (ref "R4") (pin "2") (pinfunction "2_2") (pintype "passive"))
    )
    (net (code "126") (name "Net-(LED2-A)") (class "Default")
      (node (ref "LED2") (pin "2") (pinfunction "A_2") (pintype "passive"))
      (node (ref "R5") (pin "2") (pinfunction "2_2") (pintype "passive"))
    )
    (net (code "127") (name "Net-(U1-USB0_DM)") (class "Default")
      (node (ref "R7") (pin "2") (pinfunction "2_2") (pintype "passive"))
      (node (ref "U1") (pin "20") (pinfunction "USB0_DM_20") (pintype "passive"))
    )
    (net (code "128") (name "Net-(U1-USB0_DP)") (class "Default")
      (node (ref "R6") (pin "2") (pinfunction "2_2") (pintype "passive"))
      (node (ref "U1") (pin "19") (pinfunction "USB0_DP_19") (pintype "passive"))
    )
    (net (code "129") (name "Net-(U1-VREF_OUT{slash}ADC1_SE18)") (class "Default")
      (node (ref "C14") (pin "2") (pinfunction "2_2") (pintype "passive"))
      (node (ref "U1") (pin "37") (pinfunction "VREF_OUT/ADC1_SE18_37") (pintype "passive"))
    )
    (net (code "130") (name "VCC3.3") (class "Default")
      (node (ref "F1") (pin "2") (pinfunction "2_2") (pintype "passive"))
      (node (ref "P3") (pin "31") (pinfunction "31_31") (pintype "passive"))
      (node (ref "P4") (pin "1") (pinfunction "1_1") (pintype "passive"))
      (node (ref "P4") (pin "2") (pinfunction "2_2") (pintype "passive"))
      (node (ref "P4") (pin "3") (pinfunction "3_3") (pintype "passive"))
      (node (ref "P4") (pin "4") (pinfunction "4_4") (pintype "passive"))
    )
    (net (code "131") (name "VDDA") (class "Default")
      (node (ref "C10") (pin "2") (pinfunction "2_2") (pintype "passive"))
      (node (ref "C11") (pin "2") (pinfunction "2_2") (pintype "passive"))
      (node (ref "C12") (pin "2") (pinfunction "2_2") (pintype "passive"))
      (node (ref "L1") (pin "2") (pinfunction "2_2") (pintype "passive"))
      (node (ref "R1") (pin "1") (pinfunction "1_1") (pintype "passive"))
      (node (ref "U1") (pin "31") (pinfunction "VDDA_31") (pintype "passive"))
    )
    (net (code "132") (name "VSSA") (class "Default")
      (node (ref "C10") (pin "1") (pinfunction "1_1") (pintype "passive"))
      (node (ref "C11") (pin "1") (pinfunction "1_1") (pintype "passive"))
      (node (ref "C12") (pin "1") (pinfunction "1_1") (pintype "passive"))
      (node (ref "L2") (pin "2") (pinfunction "2_2") (pintype "passive"))
      (node (ref "R2") (pin "1") (pinfunction "1_1") (pintype "passive"))
      (node (ref "U1") (pin "34") (pinfunction "VSSA_34") (pintype "passive"))
    )
  )
)
